# Gimbal_Breakout.net
KiCad netlist of a schematic drawn in EAGLE
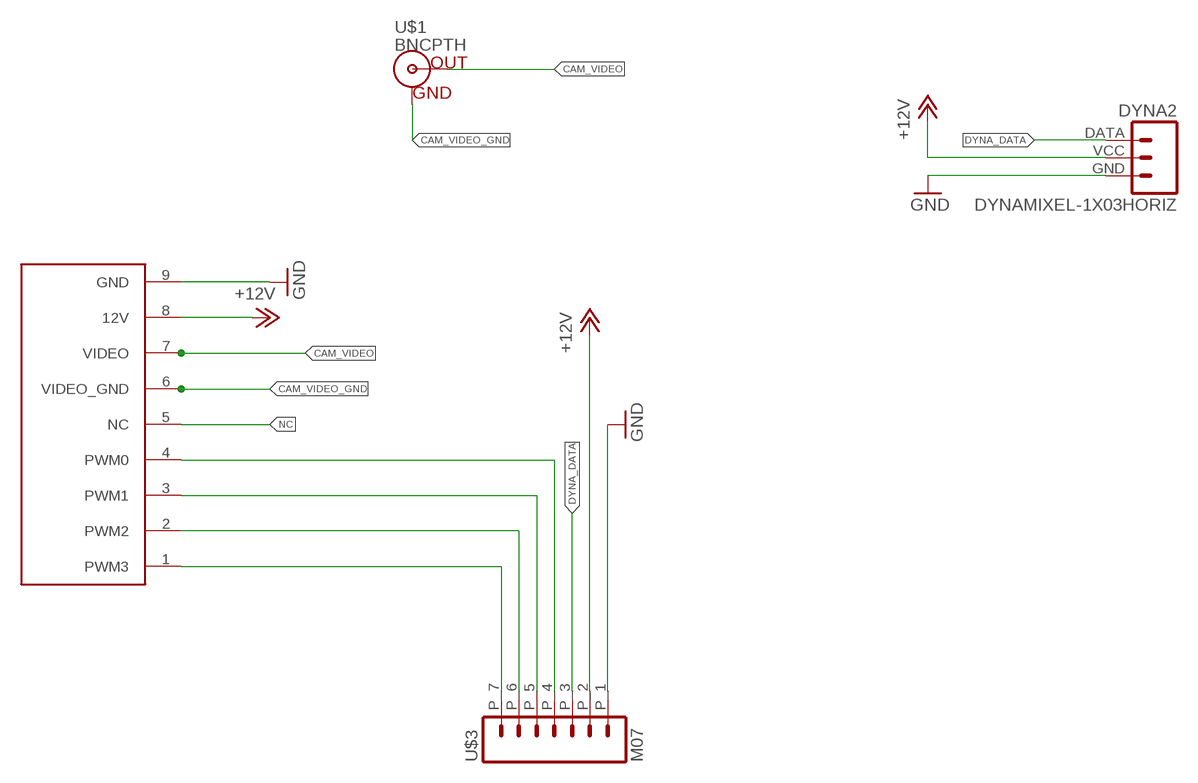
[diagram p0: schematic, sheet 1]

(export (version "E")
  (design (tool "Eeschema 10.0.6"))
  (components
    (comp (ref "DYNA2")
      (value "DYNAMIXEL-1X03HORIZ")
      (footprint "eagle-import:MLX-SPOX5268-3PIN")
      (fields (field (name "MFR") "Molex"))
      (libsource (lib "eagle-import") (part "DYNAMIXEL-1X03HORIZ"))
    )
    (comp (ref "U$1")
      (value "BNCPTH")
      (footprint "eagle-import:BNC")
      (libsource (lib "eagle-import") (part "BNCPTH"))
    )
    (comp (ref "U$3")
      (value "M07")
      (footprint "eagle-import:MOLEX_43650-07")
      (libsource (lib "eagle-import") (part "M07"))
    )
    (comp (ref "U$4")
      (value "CAMERA_BREAKOUT")
      (footprint "eagle-import:CAM_CONNECTOR")
      (libsource (lib "eagle-import") (part "CAMERA_BREAKOUT"))
    )
  )
  (nets
    (net (code "1") (name "+12V") (class "Default")
      (node (ref "DYNA2") (pin "VCC") (pinfunction "VCC_VCC") (pintype "passive"))
      (node (ref "U$3") (pin "P_2") (pinfunction "2_P_2") (pintype "passive"))
      (node (ref "U$4") (pin "8") (pinfunction "12V_8") (pintype "bidirectional"))
    )
    (net (code "2") (name "CAM_VIDEO") (class "Default")
      (node (ref "U$1") (pin "S") (pinfunction "OUT_S") (pintype "bidirectional"))
      (node (ref "U$4") (pin "7") (pinfunction "VIDEO_7") (pintype "bidirectional"))
    )
    (net (code "3") (name "CAM_VIDEO_GND") (class "Default")
      (node (ref "U$1") (pin "GND") (pinfunction "GND_GND") (pintype "bidirectional"))
      (node (ref "U$4") (pin "6") (pinfunction "VIDEO_GND_6") (pintype "bidirectional"))
    )
    (net (code "4") (name "DYNA_DATA") (class "Default")
      (node (ref "DYNA2") (pin "DATA") (pinfunction "DATA_DATA") (pintype "passive"))
      (node (ref "U$3") (pin "P_3") (pinfunction "3_P_3") (pintype "passive"))
    )
    (net (code "5") (name "GND") (class "Default")
      (node (ref "DYNA2") (pin "GND") (pinfunction "GND_GND") (pintype "passive"))
      (node (ref "U$3") (pin "P_1") (pinfunction "1_P_1") (pintype "passive"))
      (node (ref "U$4") (pin "9") (pinfunction "GND_9") (pintype "bidirectional"))
    )
    (net (code "6") (name "NC") (class "Default")
      (node (ref "U$4") (pin "5") (pinfunction "NC_5") (pintype "bidirectional"))
    )
    (net (code "7") (name "Net-(U$3-4)") (class "Default")
      (node (ref "U$3") (pin "P_4") (pinfunction "4_P_4") (pintype "passive"))
      (node (ref "U$4") (pin "4") (pinfunction "PWM0_4") (pintype "bidirectional"))
    )
    (net (code "8") (name "Net-(U$3-5)") (class "Default")
      (node (ref "U$3") (pin "P_5") (pinfunction "5_P_5") (pintype "passive"))
      (node (ref "U$4") (pin "3") (pinfunction "PWM1_3") (pintype "bidirectional"))
    )
    (net (code "9") (name "Net-(U$3-6)") (class "Default")
      (node (ref "U$3") (pin "P_6") (pinfunction "6_P_6") (pintype "passive"))
      (node (ref "U$4") (pin "2") (pinfunction "PWM2_2") (pintype "bidirectional"))
    )
    (net (code "10") (name "Net-(U$3-7)") (class "Default")
      (node (ref "U$3") (pin "P_7") (pinfunction "7_P_7") (pintype "passive"))
      (node (ref "U$4") (pin "1") (pinfunction "PWM3_1") (pintype "bidirectional"))
    )
  )
)
